# board.net
KiCad netlist of a schematic drawn in EAGLE
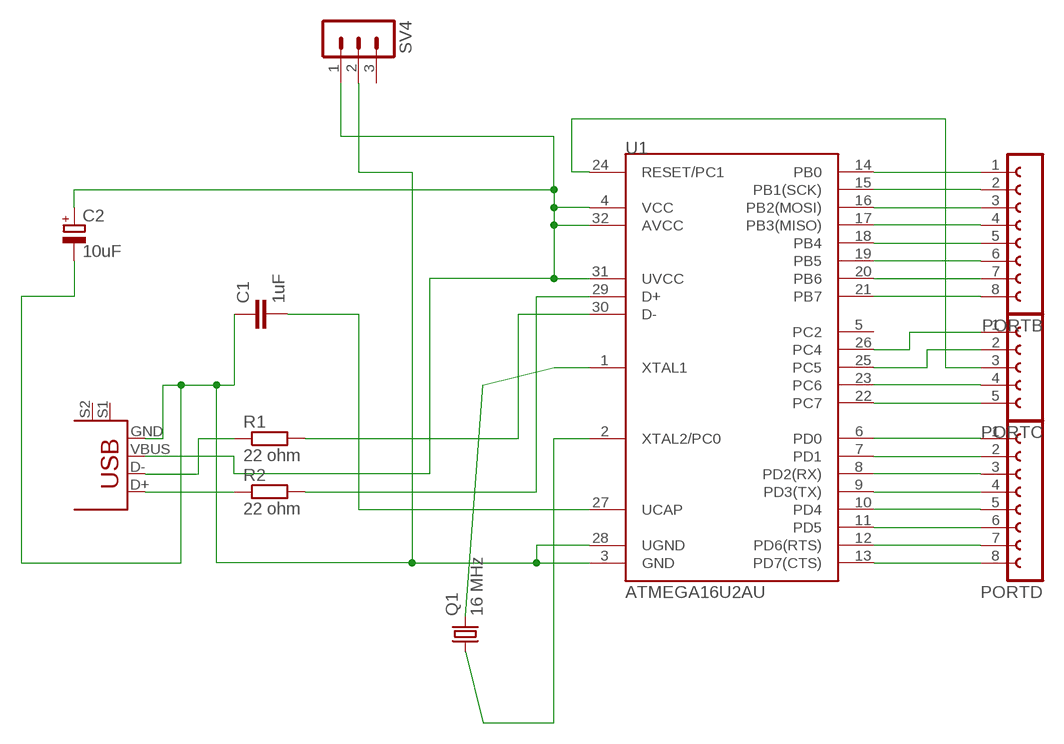
[diagram p0: schematic, sheet 1]

(export (version "E")
  (design (tool "Eeschema 10.0.6"))
  (components
    (comp (ref "C1")
      (value "1uF")
      (footprint "eagle-import:C025-024X044")
      (libsource (lib "eagle-import") (part "C-EU025-024X044"))
    )
    (comp (ref "C2")
      (value "10uF")
      (footprint "eagle-import:E1,8-4")
      (libsource (lib "eagle-import") (part "CPOL-EUE1.8-4"))
    )
    (comp (ref "PORTB")
      (value "FE08-1")
      (footprint "eagle-import:FE08")
      (libsource (lib "eagle-import") (part "FE08-1"))
    )
    (comp (ref "PORTC")
      (value "FE05-1")
      (footprint "eagle-import:FE05-1")
      (libsource (lib "eagle-import") (part "FE05-1"))
    )
    (comp (ref "PORTD")
      (value "FE08-1")
      (footprint "eagle-import:FE08")
      (libsource (lib "eagle-import") (part "FE08-1"))
    )
    (comp (ref "Q1")
      (value "16 MHz")
      (footprint "eagle-import:HC49_S")
      (libsource (lib "eagle-import") (part "CRYSTALHC49S"))
    )
    (comp (ref "R1")
      (value "22 ohm")
      (footprint "eagle-import:0207_5V")
      (libsource (lib "eagle-import") (part "R-EU_0207/5V"))
    )
    (comp (ref "R2")
      (value "22 ohm")
      (footprint "eagle-import:0207_5V")
      (libsource (lib "eagle-import") (part "R-EU_0207/5V"))
    )
    (comp (ref "SV4")
      (value "MA03-1")
      (footprint "eagle-import:MA03-1")
      (libsource (lib "eagle-import") (part "MA03-1"))
    )
    (comp (ref "U$2")
      (value "USB+SHIELD")
      (footprint "eagle-import:USB-B-PTH")
      (libsource (lib "eagle-import") (part "USB+SHIELD"))
    )
    (comp (ref "U1")
      (value "ATMEGA16U2AU")
      (footprint "eagle-import:TQFP32-08")
      (libsource (lib "eagle-import") (part "ATMEGA8U2AU"))
    )
  )
  (nets
    (net (code "1") (name "Net-(R1-Pad1)") (class "Default")
      (node (ref "R1") (pin "1") (pinfunction "1_1") (pintype "passive"))
      (node (ref "U$2") (pin "D-") (pinfunction "D-_D-") (pintype "bidirectional"))
    )
    (net (code "2") (name "Net-(R2-Pad1)") (class "Default")
      (node (ref "R2") (pin "1") (pinfunction "1_1") (pintype "passive"))
      (node (ref "U$2") (pin "D+") (pinfunction "D+_D+") (pintype "bidirectional"))
    )
    (net (code "3") (name "Net-(U1-AVCC)") (class "Default")
      (node (ref "C2") (pin "+") (pinfunction "+_+") (pintype "passive"))
      (node (ref "SV4") (pin "1") (pinfunction "1_1") (pintype "passive"))
      (node (ref "U$2") (pin "VBUS") (pinfunction "VBUS_VBUS") (pintype "bidirectional"))
      (node (ref "U1") (pin "31") (pinfunction "UVCC_31") (pintype "bidirectional"))
      (node (ref "U1") (pin "32") (pinfunction "AVCC_32") (pintype "bidirectional"))
      (node (ref "U1") (pin "4") (pinfunction "VCC_4") (pintype "bidirectional"))
    )
    (net (code "4") (name "Net-(U1-D+)") (class "Default")
      (node (ref "R2") (pin "2") (pinfunction "2_2") (pintype "passive"))
      (node (ref "U1") (pin "29") (pinfunction "D+_29") (pintype "bidirectional"))
    )
    (net (code "5") (name "Net-(U1-D-)") (class "Default")
      (node (ref "R1") (pin "2") (pinfunction "2_2") (pintype "passive"))
      (node (ref "U1") (pin "30") (pinfunction "D-_30") (pintype "bidirectional"))
    )
    (net (code "6") (name "Net-(U1-GND)") (class "Default")
      (node (ref "C1") (pin "1") (pinfunction "1_1") (pintype "passive"))
      (node (ref "C2") (pin "-") (pinfunction "-_-") (pintype "passive"))
      (node (ref "SV4") (pin "2") (pinfunction "2_2") (pintype "passive"))
      (node (ref "U$2") (pin "GND") (pinfunction "GND_GND") (pintype "bidirectional"))
      (node (ref "U1") (pin "28") (pinfunction "UGND_28") (pintype "bidirectional"))
      (node (ref "U1") (pin "3") (pinfunction "GND_3") (pintype "bidirectional"))
    )
    (net (code "7") (name "Net-(U1-PB0)") (class "Default")
      (node (ref "PORTB") (pin "1") (pinfunction "1_1") (pintype "passive"))
      (node (ref "U1") (pin "14") (pinfunction "PB0_14") (pintype "bidirectional"))
    )
    (net (code "8") (name "Net-(U1-PB1(SCK))") (class "Default")
      (node (ref "PORTB") (pin "2") (pinfunction "2_2") (pintype "passive"))
      (node (ref "U1") (pin "15") (pinfunction "PB1(SCK)_15") (pintype "bidirectional"))
    )
    (net (code "9") (name "Net-(U1-PB2(MOSI))") (class "Default")
      (node (ref "PORTB") (pin "3") (pinfunction "3_3") (pintype "passive"))
      (node (ref "U1") (pin "16") (pinfunction "PB2(MOSI)_16") (pintype "bidirectional"))
    )
    (net (code "10") (name "Net-(U1-PB3(MISO))") (class "Default")
      (node (ref "PORTB") (pin "4") (pinfunction "4_4") (pintype "passive"))
      (node (ref "U1") (pin "17") (pinfunction "PB3(MISO)_17") (pintype "bidirectional"))
    )
    (net (code "11") (name "Net-(U1-PB4)") (class "Default")
      (node (ref "PORTB") (pin "5") (pinfunction "5_5") (pintype "passive"))
      (node (ref "U1") (pin "18") (pinfunction "PB4_18") (pintype "bidirectional"))
    )
    (net (code "12") (name "Net-(U1-PB5)") (class "Default")
      (node (ref "PORTB") (pin "6") (pinfunction "6_6") (pintype "passive"))
      (node (ref "U1") (pin "19") (pinfunction "PB5_19") (pintype "bidirectional"))
    )
    (net (code "13") (name "Net-(U1-PB6)") (class "Default")
      (node (ref "PORTB") (pin "7") (pinfunction "7_7") (pintype "passive"))
      (node (ref "U1") (pin "20") (pinfunction "PB6_20") (pintype "bidirectional"))
    )
    (net (code "14") (name "Net-(U1-PB7)") (class "Default")
      (node (ref "PORTB") (pin "8") (pinfunction "8_8") (pintype "passive"))
      (node (ref "U1") (pin "21") (pinfunction "PB7_21") (pintype "bidirectional"))
    )
    (net (code "15") (name "Net-(U1-PC4)") (class "Default")
      (node (ref "PORTC") (pin "1") (pinfunction "1_1") (pintype "passive"))
      (node (ref "U1") (pin "26") (pinfunction "PC4_26") (pintype "bidirectional"))
    )
    (net (code "16") (name "Net-(U1-PC5)") (class "Default")
      (node (ref "PORTC") (pin "2") (pinfunction "2_2") (pintype "passive"))
      (node (ref "U1") (pin "25") (pinfunction "PC5_25") (pintype "bidirectional"))
    )
    (net (code "17") (name "Net-(U1-PC6)") (class "Default")
      (node (ref "PORTC") (pin "4") (pinfunction "4_4") (pintype "passive"))
      (node (ref "U1") (pin "23") (pinfunction "PC6_23") (pintype "bidirectional"))
    )
    (net (code "18") (name "Net-(U1-PC7)") (class "Default")
      (node (ref "PORTC") (pin "5") (pinfunction "5_5") (pintype "passive"))
      (node (ref "U1") (pin "22") (pinfunction "PC7_22") (pintype "bidirectional"))
    )
    (net (code "19") (name "Net-(U1-PD0)") (class "Default")
      (node (ref "PORTD") (pin "1") (pinfunction "1_1") (pintype "passive"))
      (node (ref "U1") (pin "6") (pinfunction "PD0_6") (pintype "bidirectional"))
    )
    (net (code "20") (name "Net-(U1-PD1)") (class "Default")
      (node (ref "PORTD") (pin "2") (pinfunction "2_2") (pintype "passive"))
      (node (ref "U1") (pin "7") (pinfunction "PD1_7") (pintype "bidirectional"))
    )
    (net (code "21") (name "Net-(U1-PD2(RX))") (class "Default")
      (node (ref "PORTD") (pin "3") (pinfunction "3_3") (pintype "passive"))
      (node (ref "U1") (pin "8") (pinfunction "PD2(RX)_8") (pintype "bidirectional"))
    )
    (net (code "22") (name "Net-(U1-PD3(TX))") (class "Default")
      (node (ref "PORTD") (pin "4") (pinfunction "4_4") (pintype "passive"))
      (node (ref "U1") (pin "9") (pinfunction "PD3(TX)_9") (pintype "bidirectional"))
    )
    (net (code "23") (name "Net-(U1-PD4)") (class "Default")
      (node (ref "PORTD") (pin "5") (pinfunction "5_5") (pintype "passive"))
      (node (ref "U1") (pin "10") (pinfunction "PD4_10") (pintype "bidirectional"))
    )
    (net (code "24") (name "Net-(U1-PD5)") (class "Default")
      (node (ref "PORTD") (pin "6") (pinfunction "6_6") (pintype "passive"))
      (node (ref "U1") (pin "11") (pinfunction "PD5_11") (pintype "bidirectional"))
    )
    (net (code "25") (name "Net-(U1-PD6(RTS))") (class "Default")
      (node (ref "PORTD") (pin "7") (pinfunction "7_7") (pintype "passive"))
      (node (ref "U1") (pin "12") (pinfunction "PD6(RTS)_12") (pintype "bidirectional"))
    )
    (net (code "26") (name "Net-(U1-PD7(CTS))") (class "Default")
      (node (ref "PORTD") (pin "8") (pinfunction "8_8") (pintype "passive"))
      (node (ref "U1") (pin "13") (pinfunction "PD7(CTS)_13") (pintype "bidirectional"))
    )
    (net (code "27") (name "Net-(U1-RESET{slash}PC1)") (class "Default")
      (node (ref "PORTC") (pin "3") (pinfunction "3_3") (pintype "passive"))
      (node (ref "U1") (pin "24") (pinfunction "RESET/PC1_24") (pintype "bidirectional"))
    )
    (net (code "28") (name "Net-(U1-UCAP)") (class "Default")
      (node (ref "C1") (pin "2") (pinfunction "2_2") (pintype "passive"))
      (node (ref "U1") (pin "27") (pinfunction "UCAP_27") (pintype "bidirectional"))
    )
    (net (code "29") (name "Net-(U1-XTAL1)") (class "Default")
      (node (ref "Q1") (pin "2") (pinfunction "2_2") (pintype "passive"))
      (node (ref "U1") (pin "1") (pinfunction "XTAL1_1") (pintype "bidirectional"))
    )
    (net (code "30") (name "Net-(U1-XTAL2{slash}PC0)") (class "Default")
      (node (ref "Q1") (pin "1") (pinfunction "1_1") (pintype "passive"))
      (node (ref "U1") (pin "2") (pinfunction "XTAL2/PC0_2") (pintype "bidirectional"))
    )
    (net (code "31") (name "unconnected-(SV4-Pad3)") (class "Default")
      (node (ref "SV4") (pin "3") (pinfunction "3_3") (pintype "passive"))
    )
    (net (code "32") (name "unconnected-(U$2-P$1-PadS1)") (class "Default")
      (node (ref "U$2") (pin "S1") (pinfunction "P$1_S1") (pintype "bidirectional"))
    )
    (net (code "33") (name "unconnected-(U$2-P$2-PadS2)") (class "Default")
      (node (ref "U$2") (pin "S2") (pinfunction "P$2_S2") (pintype "bidirectional"))
    )
    (net (code "34") (name "unconnected-(U1-PC2-Pad5)") (class "Default")
      (node (ref "U1") (pin "5") (pinfunction "PC2_5") (pintype "bidirectional"))
    )
  )
)
